# esquema.net
KiCad netlist of a schematic drawn in EAGLE
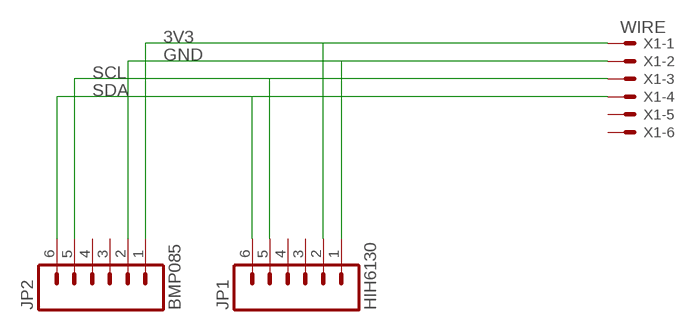
[diagram p0: schematic, sheet 1]

(export (version "E")
  (design (tool "Eeschema 10.0.6"))
  (components
    (comp (ref "JP1")
      (value "HIH6130")
      (footprint "eagle-import:1X06")
      (libsource (lib "eagle-import") (part "M06SIP"))
    )
    (comp (ref "JP2")
      (value "BMP085")
      (footprint "eagle-import:1X06")
      (libsource (lib "eagle-import") (part "M06SIP"))
    )
    (comp (ref "X1")
      (value "WIRE")
      (footprint "eagle-import:22-23-2061")
      (fields (field (name "MF") "MOLEX") (field (name "MPN") "22-23-2061"))
      (libsource (lib "eagle-import") (part "22-23-2061"))
    )
  )
  (nets
    (net (code "1") (name "/3V3") (class "Default")
      (node (ref "JP1") (pin "2") (pinfunction "2_2") (pintype "passive"))
      (node (ref "JP2") (pin "1") (pinfunction "1_1") (pintype "passive"))
      (node (ref "X1") (pin "1") (pinfunction "S_1") (pintype "passive"))
    )
    (net (code "2") (name "/GND") (class "Default")
      (node (ref "JP1") (pin "1") (pinfunction "1_1") (pintype "passive"))
      (node (ref "JP2") (pin "2") (pinfunction "2_2") (pintype "passive"))
      (node (ref "X1") (pin "2") (pinfunction "S_2") (pintype "passive"))
    )
    (net (code "3") (name "/SCL") (class "Default")
      (node (ref "JP1") (pin "5") (pinfunction "5_5") (pintype "passive"))
      (node (ref "JP2") (pin "5") (pinfunction "5_5") (pintype "passive"))
      (node (ref "X1") (pin "3") (pinfunction "S_3") (pintype "passive"))
    )
    (net (code "4") (name "/SDA") (class "Default")
      (node (ref "JP1") (pin "6") (pinfunction "6_6") (pintype "passive"))
      (node (ref "JP2") (pin "6") (pinfunction "6_6") (pintype "passive"))
      (node (ref "X1") (pin "4") (pinfunction "S_4") (pintype "passive"))
    )
    (net (code "5") (name "unconnected-(JP1-Pad3)") (class "Default")
      (node (ref "JP1") (pin "3") (pinfunction "3_3") (pintype "passive"))
    )
    (net (code "6") (name "unconnected-(JP1-Pad4)") (class "Default")
      (node (ref "JP1") (pin "4") (pinfunction "4_4") (pintype "passive"))
    )
    (net (code "7") (name "unconnected-(JP2-Pad3)") (class "Default")
      (node (ref "JP2") (pin "3") (pinfunction "3_3") (pintype "passive"))
    )
    (net (code "8") (name "unconnected-(JP2-Pad4)") (class "Default")
      (node (ref "JP2") (pin "4") (pinfunction "4_4") (pintype "passive"))
    )
    (net (code "9") (name "unconnected-(X1E-S-Pad5)") (class "Default")
      (node (ref "X1") (pin "5") (pinfunction "S_5") (pintype "passive"))
    )
    (net (code "10") (name "unconnected-(X1F-S-Pad6)") (class "Default")
      (node (ref "X1") (pin "6") (pinfunction "S_6") (pintype "passive"))
    )
  )
)
